# ESP32_module_desing.net
KiCad netlist of a schematic drawn in Altium Designer
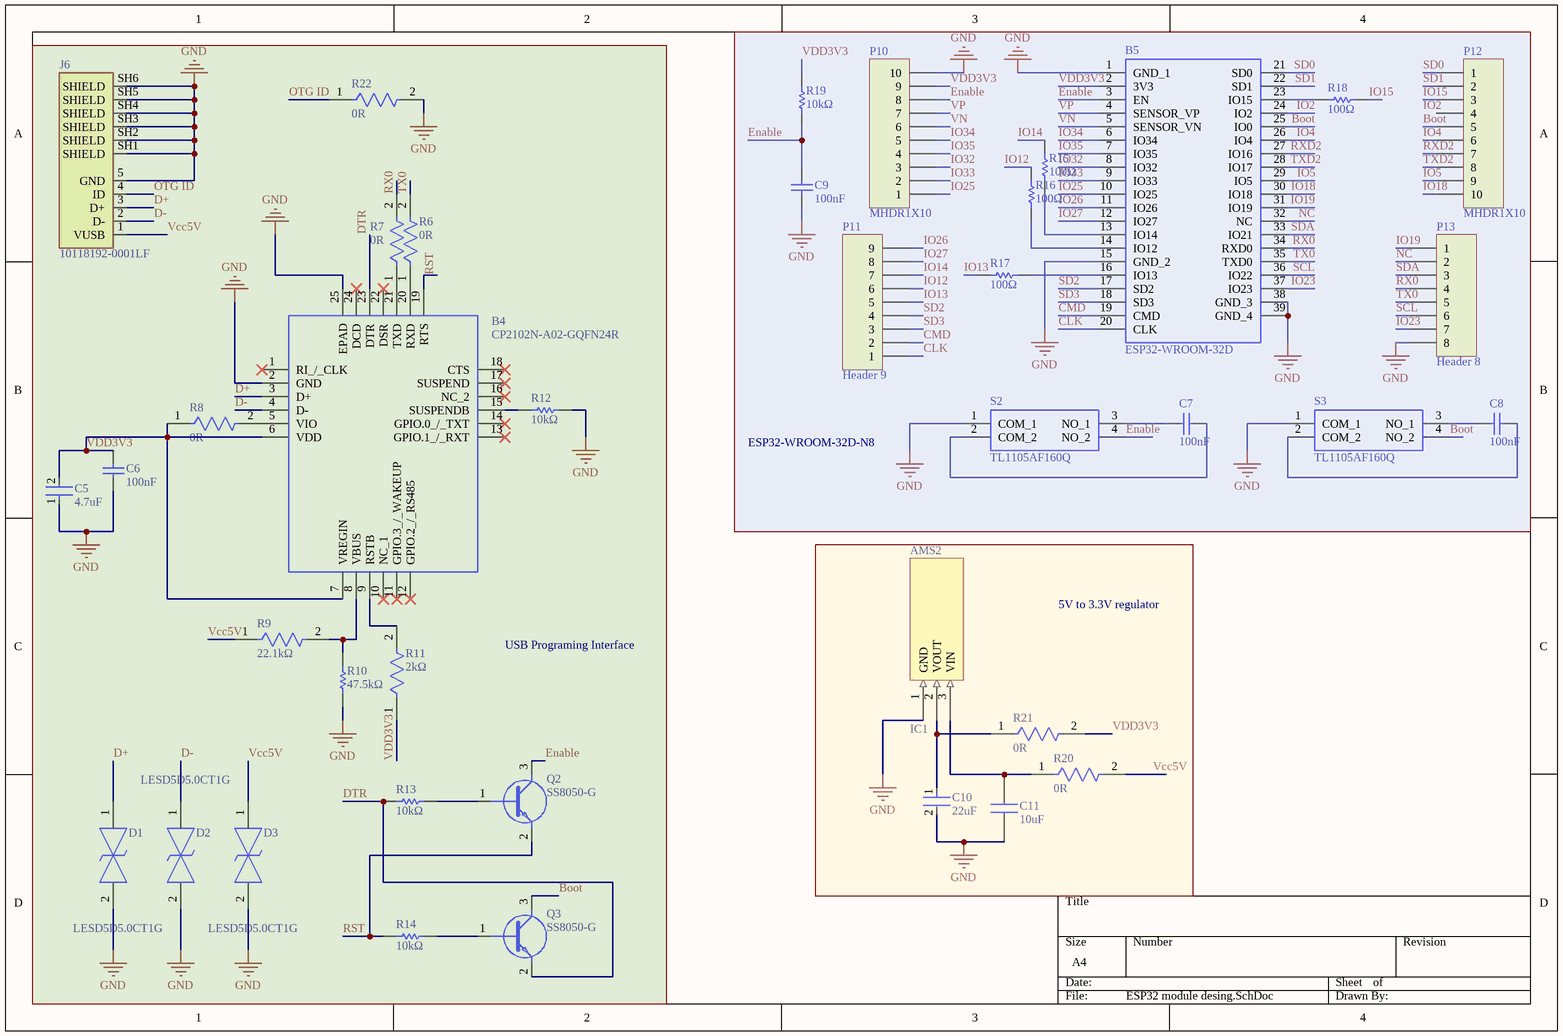
[diagram p0: ESP32 module desing.SchDoc]

(export (version "E")
  (design (tool "Eeschema 10.0.6"))
  (components
    (comp (ref "AMS2")
      (value "IC1")
      (footprint "SOT89-150P350X150-3N")
      (fields
        (field (name "MANUFACTURER") "YONGYUTAI")
        (field (name "MFR. PART #") "AMS1117-3.3")
        (field (name "LCSC PART #") "C2904742")
      )
      (libsource (lib "AMS1117-3.3") (part "IC?"))
    )
    (comp (ref "B4")
      (value "CP2102N-A02-GQFN24R")
      (footprint "QFN50P400X400X80-25N-D")
      (description "USB Interface IC USB to UART bridge - QFN24")
      (fields (field (name "MANUFACTURER") "SILICON LABS") (field (name "LCSC PART#") "C969151"))
      (libsource (lib "CP2102N-A02-GQFN24R") (part "CP2102N-A02-GQFN24R"))
    )
    (comp (ref "B5")
      (value "ESP32-WROOM-32D")
      (footprint "ESP32WROOM32D")
      (description "WiFi Modules (802.11) SMD Module, ESP32-D0WD, 32Mbits SPI flash, UART mode, PCB antenna")
      (libsource (lib "ESP32-WROOM-32D") (part "ESP32-WROOM-32D"))
    )
    (comp (ref "C5")
      (value "4.7uF")
      (footprint "FP-CL21-IPC_A")
      (description "X5R 25V 4.7uF ±10% 0805 Multilayer Ceramic Capacitors MLCC - SMD/SMT ROHS")
      (fields (field (name "LCSC PART#") "C1779") (field (name "MFR.PART #") "CL21A475KAQNNNE"))
      (libsource (lib "Altium Content Vault") (part "b4654b650e69147ec39a6b967a45e02"))
    )
    (comp (ref "C6")
      (value "100nF")
      (footprint "CAPC1050X55X23ML05T13")
      (description "X7R 100nF 16V ±10% 0402 Multilayer Ceramic Capacitors MLCC - SMD/SMT ROHS")
      (fields
        (field (name "MANUFACTURER") "Samsung Electro-Mechanics")
        (field (name "MFR.PART #") "CL05B104KO5NNNC")
      )
      (libsource (lib "Altium Content Vault") (part "CAP-NP-2"))
    )
    (comp (ref "C7")
      (value "100nF")
      (footprint "CAPC1050X55X23ML05T13")
      (description "X7R 100nF 16V ±10% 0402 Multilayer Ceramic Capacitors MLCC - SMD/SMT ROHS")
      (fields
        (field (name "MANUFACTURER") "Samsung Electro-Mechanics")
        (field (name "MFR.PART #") "CL05B104KO5NNNC")
      )
      (libsource (lib "Altium Content Vault") (part "CAP-NP-2"))
    )
    (comp (ref "C8")
      (value "100nF")
      (footprint "CAPC1050X55X23ML05T13")
      (description "X7R 100nF 16V ±10% 0402 Multilayer Ceramic Capacitors MLCC - SMD/SMT ROHS")
      (fields
        (field (name "MANUFACTURER") "Samsung Electro-Mechanics")
        (field (name "MFR.PART #") "CL05B104KO5NNNC")
      )
      (libsource (lib "Altium Content Vault") (part "CAP-NP-2"))
    )
    (comp (ref "C9")
      (value "100nF")
      (footprint "CAPC1050X55X23ML05T13")
      (description "X7R 100nF 16V ±10% 0402 Multilayer Ceramic Capacitors MLCC - SMD/SMT ROHS")
      (fields
        (field (name "MANUFACTURER") "Samsung Electro-Mechanics")
        (field (name "MFR.PART #") "CL05B104KO5NNNC")
      )
      (libsource (lib "Altium Content Vault") (part "CAP-NP-2"))
    )
    (comp (ref "C10")
      (value "22uF")
      (footprint "FP-GRM219-0_2-0_15-IPC_A")
      (description "Chip Multilayer Ceramic Capacitors for General Purpose, 0805, 22uF, X5R, 15%, 20%, 16V")
      (fields (field (name "MFR. PART #") "GRM219R61C226ME15L") (field (name "LCSC PART #") "C162295"))
      (libsource (lib "Altium Content Vault") (part "b4654b650e69147ec39a6b967a45e02"))
    )
    (comp (ref "C11")
      (value "10uF")
      (footprint "CAPC1005X70N")
      (description "6.3V 10uF X5R ±20% 0402 Multilayer Ceramic Capacitors MLCC - SMD/SMT ROHS")
      (fields
        (field (name "MANUFACTURER") "Samsung Electro-Mechanics")
        (field (name "MFR. PART #") "CL05A106MQ5NUNC")
      )
      (libsource (lib "CL05A106MQ5NUNC") (part "CL05A106MQ5NUNC"))
    )
    (comp (ref "D1")
      (value "LESD5D5.0CT1G")
      (footprint "LESD5D50CT1G")
      (description "Transient Voltage Suppressors for ESD Protection")
      (fields
        (field (name "MANUFACTURER") "UMW(Youtai Semiconductor Co., Ltd.)")
        (field (name "LCSC PART#") "C5199850")
      )
      (libsource (lib "LESD5D5.0CT1G") (part "LESD5D5.0CT1G"))
    )
    (comp (ref "D2")
      (value "LESD5D5.0CT1G")
      (footprint "LESD5D50CT1G")
      (description "Transient Voltage Suppressors for ESD Protection")
      (fields
        (field (name "MANUFACTURER") "UMW(Youtai Semiconductor Co., Ltd.)")
        (field (name "LCSC PART#") "C5199850")
      )
      (libsource (lib "LESD5D5.0CT1G") (part "LESD5D5.0CT1G"))
    )
    (comp (ref "D3")
      (value "LESD5D5.0CT1G")
      (footprint "LESD5D50CT1G")
      (description "Transient Voltage Suppressors for ESD Protection")
      (fields
        (field (name "MANUFACTURER") "UMW(Youtai Semiconductor Co., Ltd.)")
        (field (name "LCSC PART#") "C5199850")
      )
      (libsource (lib "LESD5D5.0CT1G") (part "LESD5D5.0CT1G"))
    )
    (comp (ref "J6")
      (value "10118192-0001LF")
      (footprint "AMPHENOL_10118192-0001LF")
      (description "Single Port 5 Contact Horizontal Right Angle Shielded Micro B USB 2.0 Connector")
      (fields (field (name "LCSC PART#") "C132564") (field (name "MANUFACTURER") "Amphenol ICC"))
      (libsource (lib "10118192-0001LF") (part "10118192-0001LF"))
    )
    (comp (ref "P10")
      (value "MHDR1X10")
      (footprint "MHDR1X10")
      (description "Header, 10-Pin")
      (fields (field (name "PUBLISHER") "Altium Limited"))
      (libsource (lib "") (part "MHDR1X10_1"))
    )
    (comp (ref "P11")
      (value "Header 9")
      (footprint "HDR1X9")
      (description "Header, 9-Pin")
      (fields (field (name "PUBLISHER") "Altium Limited"))
      (libsource (lib "Miscellaneous Connectors") (part "Header 9"))
    )
    (comp (ref "P12")
      (value "MHDR1X10")
      (footprint "MHDR1X10")
      (description "Header, 10-Pin")
      (fields (field (name "PUBLISHER") "Altium Limited"))
      (libsource (lib "Miscellaneous Connectors") (part "MHDR1X10"))
    )
    (comp (ref "P13")
      (value "Header 8")
      (footprint "HDR1X8")
      (description "Header, 8-Pin")
      (fields (field (name "PUBLISHER") "Altium Limited"))
      (libsource (lib "Miscellaneous Connectors") (part "Header 8"))
    )
    (comp (ref "Q2")
      (value "SS8050-G")
      (footprint "SOT95P240X115-3N")
      (fields
        (field (name "MANUFACTURER") "Jiangsu Changjing Electronics Technology Co., Ltd.")
        (field (name "LCSC PART#") "C164885")
      )
      (libsource (lib "SS8050-G") (part "SS8050-G"))
    )
    (comp (ref "Q3")
      (value "SS8050-G")
      (footprint "SOT95P240X115-3N")
      (fields
        (field (name "MANUFACTURER") "Jiangsu Changjing Electronics Technology Co., Ltd.")
        (field (name "LCSC PART#") "C164885")
      )
      (libsource (lib "SS8050-G") (part "SS8050-G"))
    )
    (comp (ref "R6")
      (value "0R")
      (footprint "FP-RC0402-0_4-IPC_A")
      (description "RES SMD 0 OHM JUMPER 1/16W 0402")
      (fields (field (name "MANUFACTURER") "Yageo") (field (name "LCSC PART #") "C106231"))
      (libsource (lib "Altium Content Vault") (part "1029c3af85768c4190bb7ad29bc67b5"))
    )
    (comp (ref "R7")
      (value "0R")
      (footprint "FP-RC0402-0_4-IPC_A")
      (description "RES SMD 0 OHM JUMPER 1/16W 0402")
      (fields (field (name "MANUFACTURER") "Yageo") (field (name "LCSC PART #") "C106231"))
      (libsource (lib "Altium Content Vault") (part "1029c3af85768c4190bb7ad29bc67b5"))
    )
    (comp (ref "R8")
      (value "0R")
      (footprint "FP-RC0402-0_4-IPC_A")
      (description "RES SMD 0 OHM JUMPER 1/16W 0402")
      (fields (field (name "MANUFACTURER") "Yageo") (field (name "LCSC PART #") "C106231"))
      (libsource (lib "Altium Content Vault") (part "1029c3af85768c4190bb7ad29bc67b5"))
    )
    (comp (ref "R9")
      (value "22.1kΩ")
      (footprint "FP-RC0402-0_4-IPC_B")
      (description "RES 22.1K OHM 1% 1/16W 0402")
      (fields (field (name "LCSC PART#") "C163478") (field (name "MANUFACTURER") "YAGEO"))
      (libsource (lib "Altium Content Vault") (part "1029c3af85768c4190bb7ad29bc67b5"))
    )
    (comp (ref "R10")
      (value "47.5kΩ")
      (footprint "RESC1005X40X25NL05T10")
      (fields
        (field (name "MFR.PART #") "RC0402FR-0747K5L")
        (field (name "MANUFACTURER") "YAGEO")
        (field (name "LCSC PART#") "C137974")
      )
      (libsource (lib "Altium Content Vault") (part "RES"))
    )
    (comp (ref "R11")
      (value "2kΩ")
      (footprint "FP-RC_L0402-MFG")
      (fields
        (field (name "LCSC PART#") "C60488")
        (field (name "MANUFACTURER") "YAGEO")
        (field (name "MFR.PART #") "RESC10050X35")
      )
      (libsource (lib "Altium Content Vault") (part "1029c3af85768c4190bb7ad29bc67b5"))
    )
    (comp (ref "R12")
      (value "10kΩ")
      (footprint "RESC1005X40X25LL05T10")
      (fields
        (field (name "MFR.PART #") "RC0402FR-0710KL")
        (field (name "MANUFACTURER") "YAGEO")
        (field (name "LCSC PART#") "C60490")
      )
      (libsource (lib "Altium Content Vault") (part "RES"))
    )
    (comp (ref "R13")
      (value "10kΩ")
      (footprint "RESC1005X40X25LL05T10")
      (fields
        (field (name "MFR.PART #") "RC0402FR-0710KL")
        (field (name "MANUFACTURER") "YAGEO")
        (field (name "LCSC PART#") "C60490")
      )
      (libsource (lib "Altium Content Vault") (part "RES"))
    )
    (comp (ref "R14")
      (value "10kΩ")
      (footprint "RESC1005X40X25LL05T10")
      (fields
        (field (name "MFR.PART #") "RC0402FR-0710KL")
        (field (name "MANUFACTURER") "YAGEO")
        (field (name "LCSC PART#") "C60490")
      )
      (libsource (lib "Altium Content Vault") (part "RES"))
    )
    (comp (ref "R15")
      (value "100Ω")
      (footprint "RESC1005X40X25ML05T10")
      (description "100Ω 62.5mW 50V ±1% -55℃~+155℃ ±100ppm/℃ 0402 Chip Resistor - Surface Mount ROHS")
      (fields (field (name "MFR.PART #") "RC0402FR-07100RL") (field (name "MANUFACTURER") "YAGEO"))
      (libsource (lib "Altium Content Vault") (part "RES"))
    )
    (comp (ref "R16")
      (value "100Ω")
      (footprint "RESC1005X40X25ML05T10")
      (description "100Ω 62.5mW 50V ±1% -55℃~+155℃ ±100ppm/℃ 0402 Chip Resistor - Surface Mount ROHS")
      (fields (field (name "MFR.PART #") "RC0402FR-07100RL") (field (name "MANUFACTURER") "YAGEO"))
      (libsource (lib "Altium Content Vault") (part "RES"))
    )
    (comp (ref "R17")
      (value "100Ω")
      (footprint "RESC1005X40X25ML05T10")
      (description "100Ω 62.5mW 50V ±1% -55℃~+155℃ ±100ppm/℃ 0402 Chip Resistor - Surface Mount ROHS")
      (fields (field (name "MFR.PART #") "RC0402FR-07100RL") (field (name "MANUFACTURER") "YAGEO"))
      (libsource (lib "Altium Content Vault") (part "RES"))
    )
    (comp (ref "R18")
      (value "100Ω")
      (footprint "RESC1005X40X25ML05T10")
      (description "100Ω 62.5mW 50V ±1% -55℃~+155℃ ±100ppm/℃ 0402 Chip Resistor - Surface Mount ROHS")
      (fields (field (name "MFR.PART #") "RC0402FR-07100RL") (field (name "MANUFACTURER") "YAGEO"))
      (libsource (lib "Altium Content Vault") (part "RES"))
    )
    (comp (ref "R19")
      (value "10kΩ")
      (footprint "RESC1005X40X25LL05T10")
      (fields
        (field (name "MFR.PART #") "RC0402FR-0710KL")
        (field (name "MANUFACTURER") "YAGEO")
        (field (name "LCSC PART#") "C60490")
      )
      (libsource (lib "Altium Content Vault") (part "RES"))
    )
    (comp (ref "R20")
      (value "0R")
      (footprint "FP-RC0402-0_4-IPC_A")
      (description "RES SMD 0 OHM JUMPER 1/16W 0402")
      (fields (field (name "MANUFACTURER") "Yageo") (field (name "LCSC PART #") "C106231"))
      (libsource (lib "Altium Content Vault") (part "1029c3af85768c4190bb7ad29bc67b5"))
    )
    (comp (ref "R21")
      (value "0R")
      (footprint "FP-RC0402-0_4-IPC_A")
      (description "RES SMD 0 OHM JUMPER 1/16W 0402")
      (fields (field (name "MANUFACTURER") "Yageo") (field (name "LCSC PART #") "C106231"))
      (libsource (lib "Altium Content Vault") (part "1029c3af85768c4190bb7ad29bc67b5"))
    )
    (comp (ref "R22")
      (value "0R")
      (footprint "FP-RC0402-0_4-IPC_A")
      (description "RES SMD 0 OHM JUMPER 1/16W 0402")
      (fields (field (name "MANUFACTURER") "Yageo") (field (name "LCSC PART #") "C106231"))
      (libsource (lib "Altium Content Vault") (part "1029c3af85768c4190bb7ad29bc67b5"))
    )
    (comp (ref "S2")
      (value "TL1105AF160Q")
      (footprint "TL1105AF160Q")
      (description "6mm 1.4mm Round Button 50mA Straight 6mm SPST 12V Plugin,6x6mm Tactile Switches ROHS")
      (fields (field (name "MANUFACTURER") "E-Switch") (field (name "LCSC PART#") "C273465"))
      (libsource (lib "TL1105AF160Q") (part "TL1105AF160Q"))
    )
    (comp (ref "S3")
      (value "TL1105AF160Q")
      (footprint "TL1105AF160Q")
      (description "6mm 1.4mm Round Button 50mA Straight 6mm SPST 12V Plugin,6x6mm Tactile Switches ROHS")
      (fields (field (name "MANUFACTURER") "E-Switch") (field (name "LCSC PART#") "C273465"))
      (libsource (lib "TL1105AF160Q") (part "TL1105AF160Q"))
    )
  )
  (nets
    (net (code "1") (name "/Boot") (class "Default")
      (node (ref "B5") (pin "25") (pinfunction "IO0_25") (pintype "passive"))
      (node (ref "P12") (pin "5") (pinfunction "5_5") (pintype "passive"))
      (node (ref "Q3") (pin "3") (pinfunction "C_3") (pintype "passive"))
      (node (ref "S3") (pin "4") (pinfunction "NO_2_4") (pintype "passive"))
    )
    (net (code "2") (name "/CLK") (class "Default")
      (node (ref "B5") (pin "20") (pinfunction "CLK_20") (pintype "passive"))
      (node (ref "P11") (pin "1") (pinfunction "1_1") (pintype "passive"))
    )
    (net (code "3") (name "/CMD") (class "Default")
      (node (ref "B5") (pin "19") (pinfunction "CMD_19") (pintype "passive"))
      (node (ref "P11") (pin "2") (pinfunction "2_2") (pintype "passive"))
    )
    (net (code "4") (name "/D+") (class "Default")
      (node (ref "B4") (pin "3") (pinfunction "D+_3") (pintype "passive"))
      (node (ref "D1") (pin "1") (pinfunction "1_1") (pintype "passive"))
      (node (ref "J6") (pin "3") (pinfunction "D+_3") (pintype "passive"))
    )
    (net (code "5") (name "/D-") (class "Default")
      (node (ref "B4") (pin "4") (pinfunction "D-_4") (pintype "passive"))
      (node (ref "D2") (pin "1") (pinfunction "1_1") (pintype "passive"))
      (node (ref "J6") (pin "2") (pinfunction "D-_2") (pintype "passive"))
    )
    (net (code "6") (name "/DTR") (class "Default")
      (node (ref "B4") (pin "23") (pinfunction "DTR_23") (pintype "passive"))
      (node (ref "Q3") (pin "2") (pinfunction "E_2") (pintype "passive"))
      (node (ref "R13") (pin "1") (pinfunction "1_1") (pintype "passive"))
    )
    (net (code "7") (name "/Enable") (class "Default")
      (node (ref "B5") (pin "3") (pinfunction "EN_3") (pintype "passive"))
      (node (ref "C9") (pin "1") (pinfunction "1_1") (pintype "passive"))
      (node (ref "P10") (pin "8") (pinfunction "8_8") (pintype "passive"))
      (node (ref "Q2") (pin "3") (pinfunction "C_3") (pintype "passive"))
      (node (ref "R19") (pin "1") (pinfunction "1_1") (pintype "passive"))
      (node (ref "S2") (pin "4") (pinfunction "NO_2_4") (pintype "passive"))
    )
    (net (code "8") (name "/IO2") (class "Default")
      (node (ref "B5") (pin "24") (pinfunction "IO2_24") (pintype "passive"))
    )
    (net (code "9") (name "/IO4") (class "Default")
      (node (ref "B5") (pin "26") (pinfunction "IO4_26") (pintype "passive"))
      (node (ref "P12") (pin "6") (pinfunction "6_6") (pintype "passive"))
    )
    (net (code "10") (name "/IO5") (class "Default")
      (node (ref "B5") (pin "29") (pinfunction "IO5_29") (pintype "passive"))
      (node (ref "P12") (pin "9") (pinfunction "9_9") (pintype "passive"))
    )
    (net (code "11") (name "/IO12") (class "Default")
      (node (ref "P11") (pin "6") (pinfunction "6_6") (pintype "passive"))
      (node (ref "R16") (pin "2") (pinfunction "2_2") (pintype "passive"))
    )
    (net (code "12") (name "/IO13") (class "Default")
      (node (ref "P11") (pin "5") (pinfunction "5_5") (pintype "passive"))
      (node (ref "R17") (pin "1") (pinfunction "1_1") (pintype "passive"))
    )
    (net (code "13") (name "/IO14") (class "Default")
      (node (ref "P11") (pin "7") (pinfunction "7_7") (pintype "passive"))
      (node (ref "R15") (pin "2") (pinfunction "2_2") (pintype "passive"))
    )
    (net (code "14") (name "/IO15") (class "Default")
      (node (ref "P12") (pin "3") (pinfunction "3_3") (pintype "passive"))
      (node (ref "R18") (pin "2") (pinfunction "2_2") (pintype "passive"))
    )
    (net (code "15") (name "/IO18") (class "Default")
      (node (ref "B5") (pin "30") (pinfunction "IO18_30") (pintype "passive"))
      (node (ref "P12") (pin "10") (pinfunction "10_10") (pintype "passive"))
    )
    (net (code "16") (name "/IO19") (class "Default")
      (node (ref "B5") (pin "31") (pinfunction "IO19_31") (pintype "passive"))
      (node (ref "P13") (pin "1") (pinfunction "1_1") (pintype "passive"))
    )
    (net (code "17") (name "/IO23") (class "Default")
      (node (ref "B5") (pin "37") (pinfunction "IO23_37") (pintype "passive"))
      (node (ref "P13") (pin "7") (pinfunction "7_7") (pintype "passive"))
    )
    (net (code "18") (name "/IO25") (class "Default")
      (node (ref "B5") (pin "10") (pinfunction "IO25_10") (pintype "passive"))
      (node (ref "P10") (pin "1") (pinfunction "1_1") (pintype "passive"))
    )
    (net (code "19") (name "/IO26") (class "Default")
      (node (ref "B5") (pin "11") (pinfunction "IO26_11") (pintype "passive"))
      (node (ref "P11") (pin "9") (pinfunction "9_9") (pintype "passive"))
    )
    (net (code "20") (name "/IO27") (class "Default")
      (node (ref "B5") (pin "12") (pinfunction "IO27_12") (pintype "passive"))
      (node (ref "P11") (pin "8") (pinfunction "8_8") (pintype "passive"))
    )
    (net (code "21") (name "/IO32") (class "Default")
      (node (ref "B5") (pin "8") (pinfunction "IO32_8") (pintype "passive"))
      (node (ref "P10") (pin "3") (pinfunction "3_3") (pintype "passive"))
    )
    (net (code "22") (name "/IO33") (class "Default")
      (node (ref "B5") (pin "9") (pinfunction "IO33_9") (pintype "passive"))
      (node (ref "P10") (pin "2") (pinfunction "2_2") (pintype "passive"))
    )
    (net (code "23") (name "/IO34") (class "Default")
      (node (ref "B5") (pin "6") (pinfunction "IO34_6") (pintype "passive"))
      (node (ref "P10") (pin "5") (pinfunction "5_5") (pintype "passive"))
    )
    (net (code "24") (name "/IO35") (class "Default")
      (node (ref "B5") (pin "7") (pinfunction "IO35_7") (pintype "passive"))
      (node (ref "P10") (pin "4") (pinfunction "4_4") (pintype "passive"))
    )
    (net (code "25") (name "/NC") (class "Default")
      (node (ref "B5") (pin "32") (pinfunction "NC_32") (pintype "passive"))
      (node (ref "P13") (pin "2") (pinfunction "2_2") (pintype "passive"))
    )
    (net (code "26") (name "/OTG ID") (class "Default")
      (node (ref "J6") (pin "4") (pinfunction "ID_4") (pintype "passive"))
      (node (ref "R22") (pin "1") (pinfunction "1_1") (pintype "passive"))
    )
    (net (code "27") (name "/RST") (class "Default")
      (node (ref "B4") (pin "19") (pinfunction "RTS_19") (pintype "passive"))
      (node (ref "Q2") (pin "2") (pinfunction "E_2") (pintype "passive"))
      (node (ref "R14") (pin "1") (pinfunction "1_1") (pintype "passive"))
    )
    (net (code "28") (name "/RX0") (class "Default")
      (node (ref "B5") (pin "34") (pinfunction "RXD0_34") (pintype "passive"))
      (node (ref "P13") (pin "4") (pinfunction "4_4") (pintype "passive"))
      (node (ref "R7") (pin "2") (pinfunction "2_2") (pintype "passive"))
    )
    (net (code "29") (name "/RXD2") (class "Default")
      (node (ref "B5") (pin "27") (pinfunction "IO16_27") (pintype "passive"))
      (node (ref "P12") (pin "7") (pinfunction "7_7") (pintype "passive"))
    )
    (net (code "30") (name "/SCL") (class "Default")
      (node (ref "B5") (pin "36") (pinfunction "IO22_36") (pintype "passive"))
      (node (ref "P13") (pin "6") (pinfunction "6_6") (pintype "passive"))
    )
    (net (code "31") (name "/SD0") (class "Default")
      (node (ref "B5") (pin "21") (pinfunction "SD0_21") (pintype "passive"))
      (node (ref "P12") (pin "1") (pinfunction "1_1") (pintype "passive"))
    )
    (net (code "32") (name "/SD1") (class "Default")
      (node (ref "B5") (pin "22") (pinfunction "SD1_22") (pintype "passive"))
      (node (ref "P12") (pin "2") (pinfunction "2_2") (pintype "passive"))
    )
    (net (code "33") (name "/SD2") (class "Default")
      (node (ref "B5") (pin "17") (pinfunction "SD2_17") (pintype "passive"))
      (node (ref "P11") (pin "4") (pinfunction "4_4") (pintype "passive"))
    )
    (net (code "34") (name "/SD3") (class "Default")
      (node (ref "B5") (pin "18") (pinfunction "SD3_18") (pintype "passive"))
      (node (ref "P11") (pin "3") (pinfunction "3_3") (pintype "passive"))
    )
    (net (code "35") (name "/SDA") (class "Default")
      (node (ref "B5") (pin "33") (pinfunction "IO21_33") (pintype "passive"))
      (node (ref "P13") (pin "3") (pinfunction "3_3") (pintype "passive"))
    )
    (net (code "36") (name "/TX0") (class "Default")
      (node (ref "B5") (pin "35") (pinfunction "TXD0_35") (pintype "passive"))
      (node (ref "P13") (pin "5") (pinfunction "5_5") (pintype "passive"))
      (node (ref "R6") (pin "2") (pinfunction "2_2") (pintype "passive"))
    )
    (net (code "37") (name "/TXD2") (class "Default")
      (node (ref "B5") (pin "28") (pinfunction "IO17_28") (pintype "passive"))
      (node (ref "P12") (pin "8") (pinfunction "8_8") (pintype "passive"))
    )
    (net (code "38") (name "/VDD3V3") (class "Default")
      (node (ref "B4") (pin "6") (pinfunction "VDD_6") (pintype "passive"))
      (node (ref "B4") (pin "7") (pinfunction "VREGIN_7") (pintype "passive"))
      (node (ref "B5") (pin "2") (pinfunction "3V3_2") (pintype "passive"))
      (node (ref "C5") (pin "2") (pinfunction "2_2") (pintype "passive"))
      (node (ref "C6") (pin "2") (pinfunction "2_2") (pintype "passive"))
      (node (ref "P10") (pin "9") (pinfunction "9_9") (pintype "passive"))
      (node (ref "R11") (pin "1") (pinfunction "1_1") (pintype "passive"))
      (node (ref "R19") (pin "2") (pinfunction "2_2") (pintype "passive"))
      (node (ref "R21") (pin "2") (pinfunction "2_2") (pintype "passive"))
      (node (ref "R8") (pin "1") (pinfunction "1_1") (pintype "passive"))
    )
    (net (code "39") (name "/VN") (class "Default")
      (node (ref "B5") (pin "5") (pinfunction "SENSOR_VN_5") (pintype "passive"))
      (node (ref "P10") (pin "6") (pinfunction "6_6") (pintype "passive"))
    )
    (net (code "40") (name "/VP") (class "Default")
      (node (ref "B5") (pin "4") (pinfunction "SENSOR_VP_4") (pintype "passive"))
      (node (ref "P10") (pin "7") (pinfunction "7_7") (pintype "passive"))
    )
    (net (code "41") (name "/Vcc5V") (class "Default")
      (node (ref "D3") (pin "1") (pinfunction "1_1") (pintype "passive"))
      (node (ref "J6") (pin "1") (pinfunction "VUSB_1") (pintype "passive"))
      (node (ref "R20") (pin "2") (pinfunction "2_2") (pintype "passive"))
      (node (ref "R9") (pin "1") (pinfunction "1_1") (pintype "passive"))
    )
    (net (code "42") (name "GND") (class "Default")
      (node (ref "AMS2") (pin "1") (pinfunction "GND_1") (pintype "input"))
      (node (ref "B4") (pin "2") (pinfunction "GND_2") (pintype "passive"))
      (node (ref "B4") (pin "25") (pinfunction "EPAD_25") (pintype "passive"))
      (node (ref "B5") (pin "1") (pinfunction "GND_1_1") (pintype "passive"))
      (node (ref "B5") (pin "15") (pinfunction "GND_2_15") (pintype "passive"))
      (node (ref "B5") (pin "38") (pinfunction "GND_3_38") (pintype "passive"))
      (node (ref "B5") (pin "39") (pinfunction "GND_4_39") (pintype "passive"))
      (node (ref "C10") (pin "2") (pinfunction "2_2") (pintype "passive"))
      (node (ref "C11") (pin "1") (pinfunction "1_1") (pintype "passive"))
      (node (ref "C5") (pin "1") (pinfunction "1_1") (pintype "passive"))
      (node (ref "C6") (pin "1") (pinfunction "1_1") (pintype "passive"))
      (node (ref "C9") (pin "2") (pinfunction "2_2") (pintype "passive"))
      (node (ref "D1") (pin "2") (pinfunction "2_2") (pintype "passive"))
      (node (ref "D2") (pin "2") (pinfunction "2_2") (pintype "passive"))
      (node (ref "D3") (pin "2") (pinfunction "2_2") (pintype "passive"))
      (node (ref "J6") (pin "5") (pinfunction "GND_5") (pintype "passive"))
      (node (ref "J6") (pin "SH1") (pinfunction "SHIELD_SH1") (pintype "passive"))
      (node (ref "J6") (pin "SH2") (pinfunction "SHIELD_SH2") (pintype "passive"))
      (node (ref "J6") (pin "SH3") (pinfunction "SHIELD_SH3") (pintype "passive"))
      (node (ref "J6") (pin "SH4") (pinfunction "SHIELD_SH4") (pintype "passive"))
      (node (ref "J6") (pin "SH5") (pinfunction "SHIELD_SH5") (pintype "passive"))
      (node (ref "J6") (pin "SH6") (pinfunction "SHIELD_SH6") (pintype "passive"))
      (node (ref "P10") (pin "10") (pinfunction "10_10") (pintype "passive"))
      (node (ref "P13") (pin "8") (pinfunction "8_8") (pintype "passive"))
      (node (ref "R10") (pin "1") (pinfunction "1_1") (pintype "passive"))
      (node (ref "R12") (pin "2") (pinfunction "2_2") (pintype "passive"))
      (node (ref "R22") (pin "2") (pinfunction "2_2") (pintype "passive"))
      (node (ref "S2") (pin "1") (pinfunction "COM_1_1") (pintype "passive"))
      (node (ref "S3") (pin "1") (pinfunction "COM_1_1") (pintype "passive"))
    )
    (net (code "43") (name "Net-(AMS2-VIN)") (class "Default")
      (node (ref "AMS2") (pin "3") (pinfunction "VIN_3") (pintype "input"))
      (node (ref "C11") (pin "2") (pinfunction "2_2") (pintype "passive"))
      (node (ref "R20") (pin "1") (pinfunction "1_1") (pintype "passive"))
    )
    (net (code "44") (name "Net-(AMS2-VOUT)") (class "Default")
      (node (ref "AMS2") (pin "2") (pinfunction "VOUT_2") (pintype "input"))
      (node (ref "C10") (pin "1") (pinfunction "1_1") (pintype "passive"))
      (node (ref "R21") (pin "1") (pinfunction "1_1") (pintype "passive"))
    )
    (net (code "45") (name "Net-(B4-RSTB)") (class "Default")
      (node (ref "B4") (pin "9") (pinfunction "RSTB_9") (pintype "passive"))
      (node (ref "R11") (pin "2") (pinfunction "2_2") (pintype "passive"))
    )
    (net (code "46") (name "Net-(B4-RXD)") (class "Default")
      (node (ref "B4") (pin "20") (pinfunction "RXD_20") (pintype "passive"))
      (node (ref "R6") (pin "1") (pinfunction "1_1") (pintype "passive"))
    )
    (net (code "47") (name "Net-(B4-SUSPENDB)") (class "Default")
      (node (ref "B4") (pin "15") (pinfunction "SUSPENDB_15") (pintype "passive"))
      (node (ref "R12") (pin "1") (pinfunction "1_1") (pintype "passive"))
    )
    (net (code "48") (name "Net-(B4-TXD)") (class "Default")
      (node (ref "B4") (pin "21") (pinfunction "TXD_21") (pintype "passive"))
      (node (ref "R7") (pin "1") (pinfunction "1_1") (pintype "passive"))
    )
    (net (code "49") (name "Net-(B4-VBUS)") (class "Default")
      (node (ref "B4") (pin "8") (pinfunction "VBUS_8") (pintype "passive"))
      (node (ref "R10") (pin "2") (pinfunction "2_2") (pintype "passive"))
      (node (ref "R9") (pin "2") (pinfunction "2_2") (pintype "passive"))
    )
    (net (code "50") (name "Net-(B4-VIO)") (class "Default")
      (node (ref "B4") (pin "5") (pinfunction "VIO_5") (pintype "passive"))
      (node (ref "R8") (pin "2") (pinfunction "2_2") (pintype "passive"))
    )
    (net (code "51") (name "Net-(B5-IO12)") (class "Default")
      (node (ref "B5") (pin "14") (pinfunction "IO12_14") (pintype "passive"))
      (node (ref "R16") (pin "1") (pinfunction "1_1") (pintype "passive"))
    )
    (net (code "52") (name "Net-(B5-IO13)") (class "Default")
      (node (ref "B5") (pin "16") (pinfunction "IO13_16") (pintype "passive"))
      (node (ref "R17") (pin "2") (pinfunction "2_2") (pintype "passive"))
    )
    (net (code "53") (name "Net-(B5-IO14)") (class "Default")
      (node (ref "B5") (pin "13") (pinfunction "IO14_13") (pintype "passive"))
      (node (ref "R15") (pin "1") (pinfunction "1_1") (pintype "passive"))
    )
    (net (code "54") (name "Net-(B5-IO15)") (class "Default")
      (node (ref "B5") (pin "23") (pinfunction "IO15_23") (pintype "passive"))
      (node (ref "R18") (pin "1") (pinfunction "1_1") (pintype "passive"))
    )
    (net (code "55") (name "Net-(Q2-B)") (class "Default")
      (node (ref "Q2") (pin "1") (pinfunction "B_1") (pintype "passive"))
      (node (ref "R13") (pin "2") (pinfunction "2_2") (pintype "passive"))
    )
    (net (code "56") (name "Net-(Q3-B)") (class "Default")
      (node (ref "Q3") (pin "1") (pinfunction "B_1") (pintype "passive"))
      (node (ref "R14") (pin "2") (pinfunction "2_2") (pintype "passive"))
    )
    (net (code "57") (name "Net-(S2-COM_2)") (class "Default")
      (node (ref "C7") (pin "1") (pinfunction "1_1") (pintype "passive"))
      (node (ref "S2") (pin "2") (pinfunction "COM_2_2") (pintype "passive"))
    )
    (net (code "58") (name "Net-(S2-NO_1)") (class "Default")
      (node (ref "C7") (pin "2") (pinfunction "2_2") (pintype "passive"))
      (node (ref "S2") (pin "3") (pinfunction "NO_1_3") (pintype "passive"))
    )
    (net (code "59") (name "Net-(S3-COM_2)") (class "Default")
      (node (ref "C8") (pin "1") (pinfunction "1_1") (pintype "passive"))
      (node (ref "S3") (pin "2") (pinfunction "COM_2_2") (pintype "passive"))
    )
    (net (code "60") (name "Net-(S3-NO_1)") (class "Default")
      (node (ref "C8") (pin "2") (pinfunction "2_2") (pintype "passive"))
      (node (ref "S3") (pin "3") (pinfunction "NO_1_3") (pintype "passive"))
    )
    (net (code "61") (name "unconnected-(B4-CTS-Pad18)") (class "Default")
      (node (ref "B4") (pin "18") (pinfunction "CTS_18") (pintype "passive+no_connect"))
    )
    (net (code "62") (name "unconnected-(B4-DCD-Pad24)") (class "Default")
      (node (ref "B4") (pin "24") (pinfunction "DCD_24") (pintype "passive+no_connect"))
    )
    (net (code "63") (name "unconnected-(B4-DSR-Pad22)") (class "Default")
      (node (ref "B4") (pin "22") (pinfunction "DSR_22") (pintype "passive+no_connect"))
    )
    (net (code "64") (name "unconnected-(B4-GPIO.0_{slash}_TXT-Pad14)") (class "Default")
      (node (ref "B4") (pin "14") (pinfunction "GPIO.0_/_TXT_14") (pintype "passive+no_connect"))
    )
    (net (code "65") (name "unconnected-(B4-GPIO.1_{slash}_RXT-Pad13)") (class "Default")
      (node (ref "B4") (pin "13") (pinfunction "GPIO.1_/_RXT_13") (pintype "passive+no_connect"))
    )
    (net (code "66") (name "unconnected-(B4-GPIO.2_{slash}_RS485-Pad12)") (class "Default")
      (node (ref "B4") (pin "12") (pinfunction "GPIO.2_/_RS485_12") (pintype "passive+no_connect"))
    )
    (net (code "67") (name "unconnected-(B4-GPIO.3_{slash}_WAKEUP-Pad11)") (class "Default")
      (node (ref "B4") (pin "11") (pinfunction "GPIO.3_/_WAKEUP_11") (pintype "passive+no_connect"))
    )
    (net (code "68") (name "unconnected-(B4-NC_1-Pad10)") (class "Default")
      (node (ref "B4") (pin "10") (pinfunction "NC_1_10") (pintype "passive+no_connect"))
    )
    (net (code "69") (name "unconnected-(B4-NC_2-Pad16)") (class "Default")
      (node (ref "B4") (pin "16") (pinfunction "NC_2_16") (pintype "passive+no_connect"))
    )
    (net (code "70") (name "unconnected-(B4-RI_{slash}_CLK-Pad1)") (class "Default")
      (node (ref "B4") (pin "1") (pinfunction "RI_/_CLK_1") (pintype "passive+no_connect"))
    )
    (net (code "71") (name "unconnected-(B4-SUSPEND-Pad17)") (class "Default")
      (node (ref "B4") (pin "17") (pinfunction "SUSPEND_17") (pintype "passive+no_connect"))
    )
    (net (code "72") (name "unconnected-(P12-Pad4)") (class "Default")
      (node (ref "P12") (pin "4") (pinfunction "4_4") (pintype "passive"))
    )
  )
)
